# motor_line.net
KiCad netlist of a schematic drawn in EAGLE
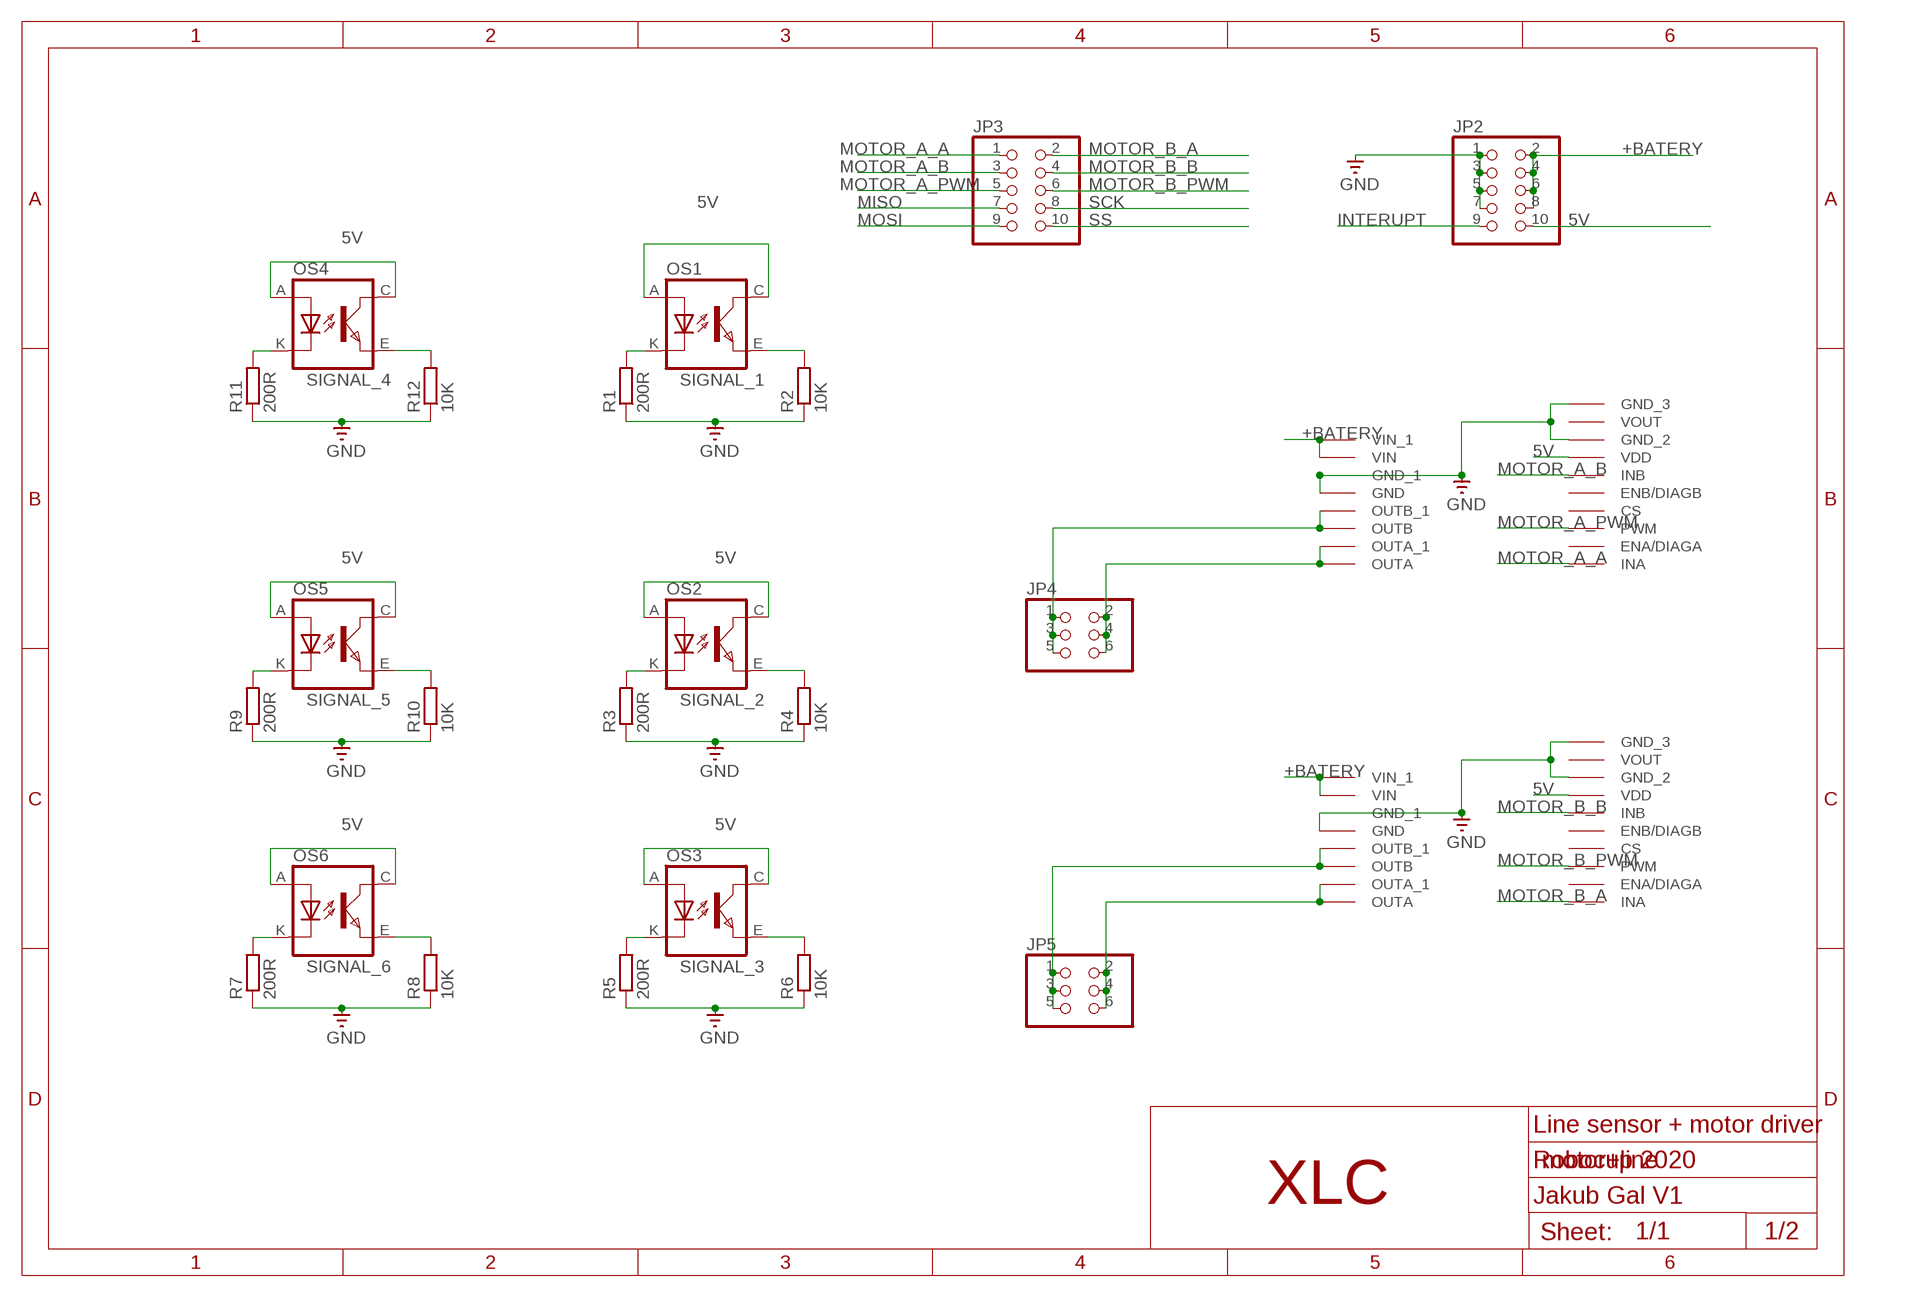
[diagram p0: schematic, sheet 1, part 1 of 2]
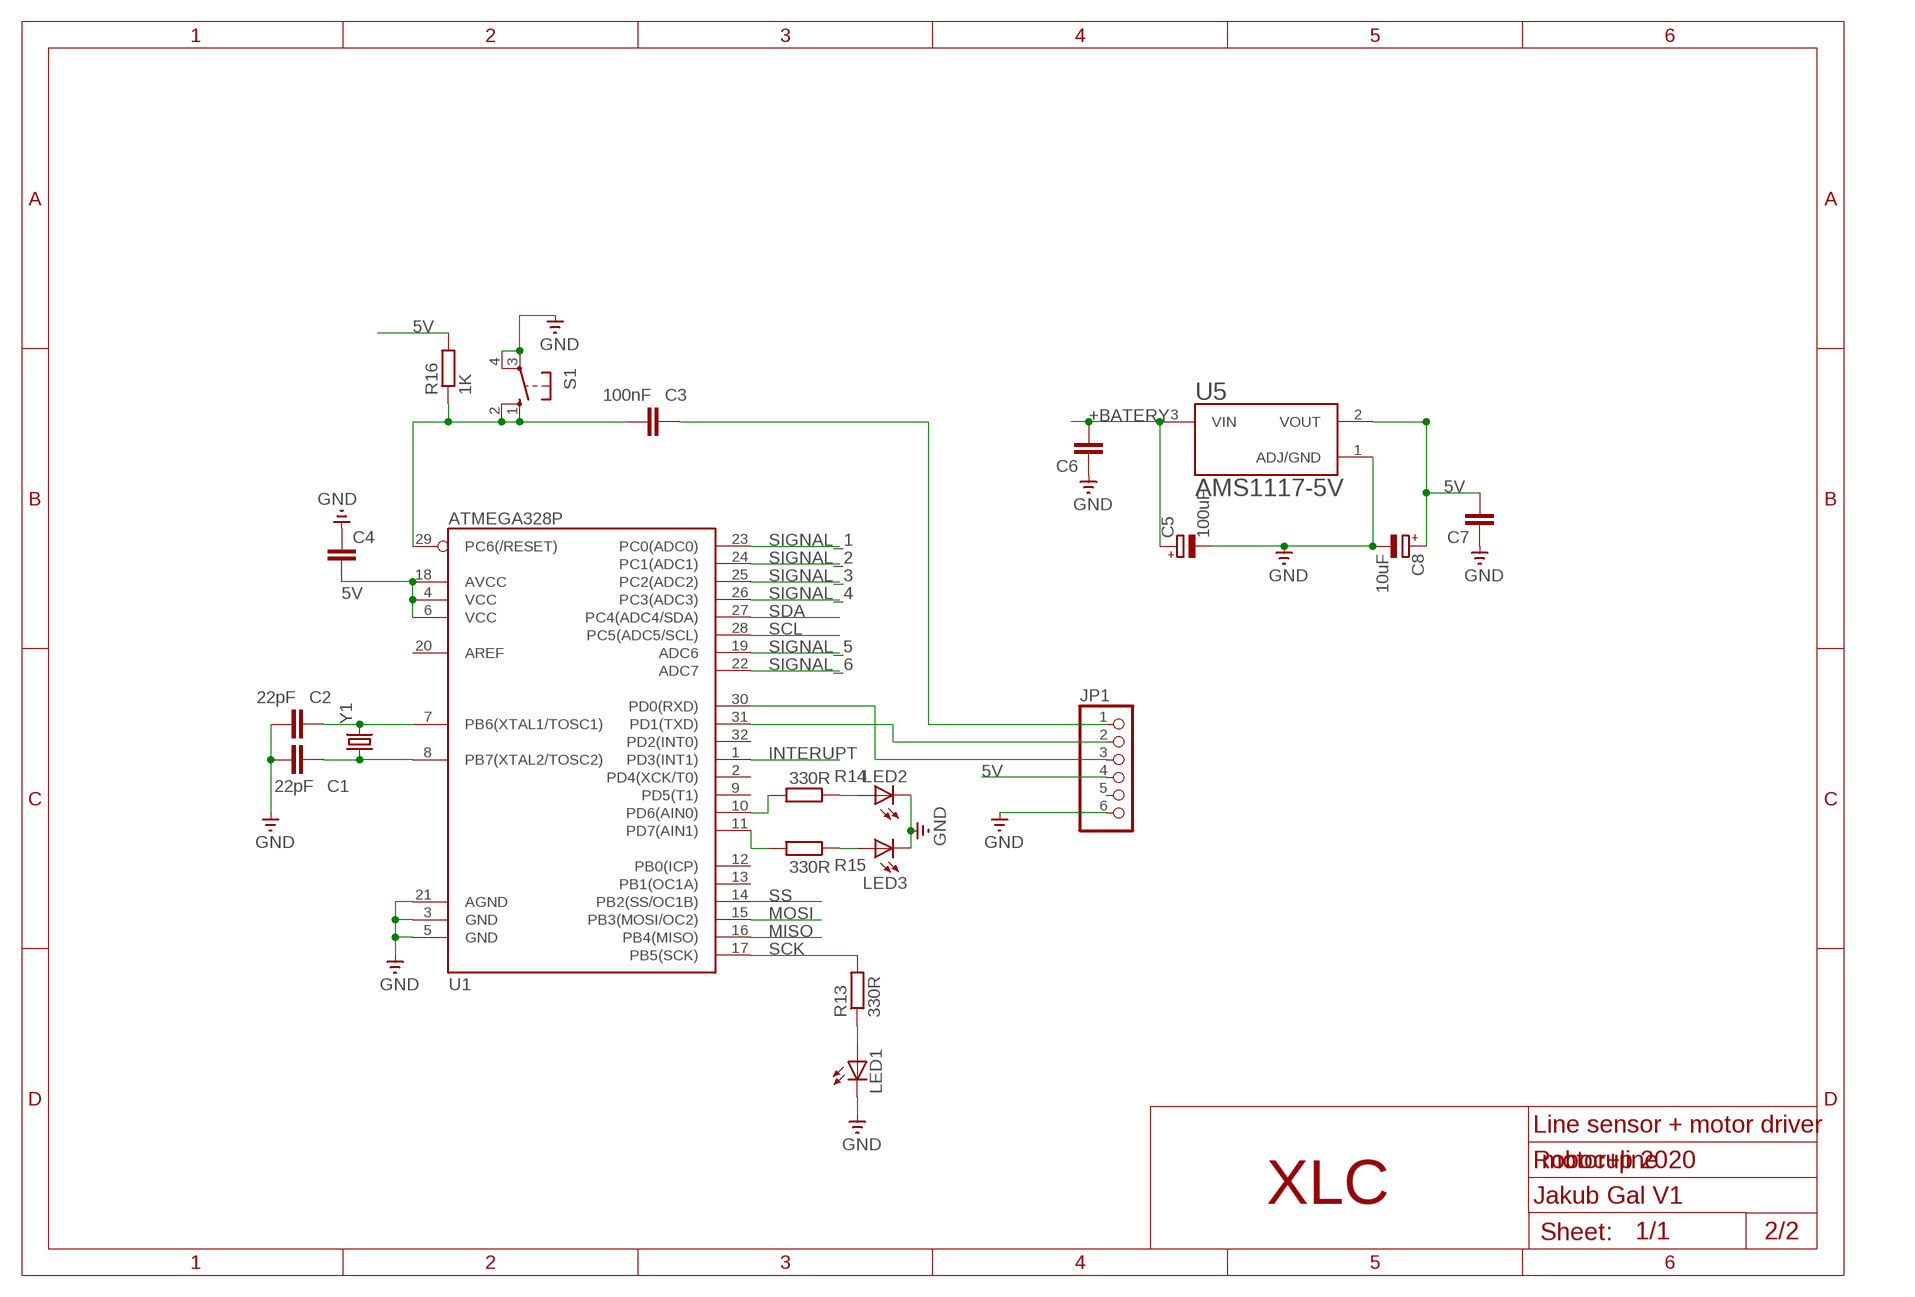
[diagram p1: schematic, sheet 1, part 2 of 2]

(export (version "E")
  (design (tool "Eeschema 10.0.6"))
  (components
    (comp (ref "C1")
      (value "22pF")
      (footprint "eagle-import:C0603")
      (libsource (lib "eagle-import") (part "C-EUC0603"))
    )
    (comp (ref "C2")
      (value "22pF")
      (footprint "eagle-import:C0603")
      (libsource (lib "eagle-import") (part "C-EUC0603"))
    )
    (comp (ref "C3")
      (value "100nF")
      (footprint "eagle-import:C0603")
      (libsource (lib "eagle-import") (part "C-EUC0603"))
    )
    (comp (ref "C4")
      (value "C-EUC0603")
      (footprint "eagle-import:C0603")
      (libsource (lib "eagle-import") (part "rcl_334_C-EUC0603"))
    )
    (comp (ref "C5")
      (value "100uF")
      (footprint "eagle-import:UD-6,3X7,7_NICHICON")
      (libsource (lib "eagle-import") (part "CPOL-EUUD-6,3X7,7"))
    )
    (comp (ref "C6")
      (value "C-EUC0603")
      (footprint "eagle-import:C0603")
      (libsource (lib "eagle-import") (part "rcl_334_C-EUC0603"))
    )
    (comp (ref "C7")
      (value "C-EUC0603")
      (footprint "eagle-import:C0603")
      (libsource (lib "eagle-import") (part "rcl_334_C-EUC0603"))
    )
    (comp (ref "C8")
      (value "10uF")
      (footprint "eagle-import:UD-4X5,8_NICHICON")
      (libsource (lib "eagle-import") (part "CPOL-EUUD-4X5,8"))
    )
    (comp (ref "JP1")
      (value "PINHD-1X6/90")
      (footprint "eagle-import:1X06_90")
      (libsource (lib "eagle-import") (part "PINHD-1X6/90"))
    )
    (comp (ref "JP2")
      (value "PINHD-2X5")
      (footprint "eagle-import:2X05")
      (libsource (lib "eagle-import") (part "PINHD-2X5"))
    )
    (comp (ref "JP3")
      (value "PINHD-2X5")
      (footprint "eagle-import:2X05")
      (libsource (lib "eagle-import") (part "PINHD-2X5"))
    )
    (comp (ref "JP4")
      (value "PINHD-2X3")
      (footprint "eagle-import:2X03")
      (libsource (lib "eagle-import") (part "PINHD-2X3"))
    )
    (comp (ref "JP5")
      (value "PINHD-2X3")
      (footprint "eagle-import:2X03")
      (libsource (lib "eagle-import") (part "PINHD-2X3"))
    )
    (comp (ref "LED1")
      (value "LEDCHIPLED_0603")
      (footprint "eagle-import:CHIPLED_0603")
      (libsource (lib "eagle-import") (part "LEDCHIPLED_0603"))
    )
    (comp (ref "LED2")
      (value "LEDCHIPLED_0603")
      (footprint "eagle-import:CHIPLED_0603")
      (libsource (lib "eagle-import") (part "LEDCHIPLED_0603"))
    )
    (comp (ref "LED3")
      (value "LEDCHIPLED_0603")
      (footprint "eagle-import:CHIPLED_0603")
      (libsource (lib "eagle-import") (part "LEDCHIPLED_0603"))
    )
    (comp (ref "OS1")
      (value "TCRT5000")
      (footprint "eagle-import:TCRT5000")
      (libsource (lib "eagle-import") (part "TCRT5000"))
    )
    (comp (ref "OS2")
      (value "TCRT5000")
      (footprint "eagle-import:TCRT5000")
      (libsource (lib "eagle-import") (part "TCRT5000"))
    )
    (comp (ref "OS3")
      (value "TCRT5000")
      (footprint "eagle-import:TCRT5000")
      (libsource (lib "eagle-import") (part "TCRT5000"))
    )
    (comp (ref "OS4")
      (value "TCRT5000")
      (footprint "eagle-import:TCRT5000")
      (fields (field (name "SPICEPREFIX") "O"))
      (libsource (lib "eagle-import") (part "TCRT5000"))
    )
    (comp (ref "OS5")
      (value "TCRT5000")
      (footprint "eagle-import:TCRT5000")
      (libsource (lib "eagle-import") (part "TCRT5000"))
    )
    (comp (ref "OS6")
      (value "TCRT5000")
      (footprint "eagle-import:TCRT5000")
      (fields (field (name "SPICEPREFIX") "O"))
      (libsource (lib "eagle-import") (part "TCRT5000"))
    )
    (comp (ref "R1")
      (value "200R")
      (footprint "eagle-import:R0603")
      (libsource (lib "eagle-import") (part "R-EU_R0603"))
    )
    (comp (ref "R2")
      (value "10K")
      (footprint "eagle-import:R0603")
      (libsource (lib "eagle-import") (part "R-EU_R0603"))
    )
    (comp (ref "R3")
      (value "200R")
      (footprint "eagle-import:R0603")
      (libsource (lib "eagle-import") (part "R-EU_R0603"))
    )
    (comp (ref "R4")
      (value "10K")
      (footprint "eagle-import:R0603")
      (libsource (lib "eagle-import") (part "R-EU_R0603"))
    )
    (comp (ref "R5")
      (value "200R")
      (footprint "eagle-import:R0603")
      (libsource (lib "eagle-import") (part "R-EU_R0603"))
    )
    (comp (ref "R6")
      (value "10K")
      (footprint "eagle-import:R0603")
      (libsource (lib "eagle-import") (part "R-EU_R0603"))
    )
    (comp (ref "R7")
      (value "200R")
      (footprint "eagle-import:R0603")
      (libsource (lib "eagle-import") (part "R-EU_R0603"))
    )
    (comp (ref "R8")
      (value "10K")
      (footprint "eagle-import:R0603")
      (libsource (lib "eagle-import") (part "R-EU_R0603"))
    )
    (comp (ref "R9")
      (value "200R")
      (footprint "eagle-import:R0603")
      (libsource (lib "eagle-import") (part "R-EU_R0603"))
    )
    (comp (ref "R10")
      (value "10K")
      (footprint "eagle-import:R0603")
      (libsource (lib "eagle-import") (part "R-EU_R0603"))
    )
    (comp (ref "R11")
      (value "200R")
      (footprint "eagle-import:R0603")
      (libsource (lib "eagle-import") (part "R-EU_R0603"))
    )
    (comp (ref "R12")
      (value "10K")
      (footprint "eagle-import:R0603")
      (libsource (lib "eagle-import") (part "R-EU_R0603"))
    )
    (comp (ref "R13")
      (value "330R")
      (footprint "eagle-import:R0603")
      (libsource (lib "eagle-import") (part "R-EU_R0603"))
    )
    (comp (ref "R14")
      (value "330R")
      (footprint "eagle-import:R0603")
      (libsource (lib "eagle-import") (part "R-EU_R0603"))
    )
    (comp (ref "R15")
      (value "330R")
      (footprint "eagle-import:R0603")
      (libsource (lib "eagle-import") (part "R-EU_R0603"))
    )
    (comp (ref "R16")
      (value "1K")
      (footprint "eagle-import:R0603")
      (libsource (lib "eagle-import") (part "R-EU_R0603"))
    )
    (comp (ref "S1")
      (value "10-XX")
      (footprint "eagle-import:B3F-10XX")
      (fields (field (name "MPN") "B3F-1000"))
      (libsource (lib "eagle-import") (part "10-XX"))
    )
    (comp (ref "U$1")
      (value "MOTOR_DRIVER")
      (footprint "eagle-import:MOTOR_DRIVER")
      (libsource (lib "eagle-import") (part "MOTOR_DRIVER"))
    )
    (comp (ref "U$2")
      (value "MOTOR_DRIVER")
      (footprint "eagle-import:MOTOR_DRIVER")
      (libsource (lib "eagle-import") (part "MOTOR_DRIVER"))
    )
    (comp (ref "U1")
      (value "ATMEGA328P")
      (footprint "eagle-import:TQFP32-08")
      (libsource (lib "eagle-import") (part "ATMEGA328_SMT"))
    )
    (comp (ref "U5")
      (value "AMS1117-5V")
      (footprint "eagle-import:SOT229P700X180-4N")
      (fields (field (name "MF") "Advanced Monolithic Systems") (field (name "MP") "AMS1117-3.3"))
      (libsource (lib "eagle-import") (part "AMS1117-3.3"))
    )
    (comp (ref "Y1")
      (value "CRYSTALHC49US")
      (footprint "eagle-import:HC49US")
      (libsource (lib "eagle-import") (part "CRYSTALHC49US"))
    )
  )
  (nets
    (net (code "1") (name "/+BATERY") (class "Default")
      (node (ref "C5") (pin "+") (pinfunction "+_+") (pintype "passive"))
      (node (ref "C6") (pin "2") (pinfunction "2_2") (pintype "passive"))
      (node (ref "JP2") (pin "2") (pinfunction "2_2") (pintype "passive"))
      (node (ref "JP2") (pin "4") (pinfunction "4_4") (pintype "passive"))
      (node (ref "JP2") (pin "6") (pinfunction "6_6") (pintype "passive"))
      (node (ref "JP2") (pin "8") (pinfunction "8_8") (pintype "passive"))
      (node (ref "U$1") (pin "VIN") (pinfunction "VIN_VIN") (pintype "bidirectional"))
      (node (ref "U$1") (pin "VIN_1") (pinfunction "VIN_1_VIN_1") (pintype "bidirectional"))
      (node (ref "U$2") (pin "VIN") (pinfunction "VIN_VIN") (pintype "bidirectional"))
      (node (ref "U$2") (pin "VIN_1") (pinfunction "VIN_1_VIN_1") (pintype "bidirectional"))
      (node (ref "U5") (pin "3") (pinfunction "VIN_3") (pintype "input"))
    )
    (net (code "2") (name "/5V") (class "Default")
      (node (ref "C4") (pin "2") (pinfunction "2_2") (pintype "passive"))
      (node (ref "C7") (pin "2") (pinfunction "2_2") (pintype "passive"))
      (node (ref "C8") (pin "+") (pinfunction "+_+") (pintype "passive"))
      (node (ref "JP1") (pin "4") (pinfunction "4_4") (pintype "passive"))
      (node (ref "JP2") (pin "10") (pinfunction "10_10") (pintype "passive"))
      (node (ref "OS1") (pin "A") (pinfunction "ANODE_A") (pintype "passive"))
      (node (ref "OS1") (pin "C") (pinfunction "COLLECTOR_C") (pintype "passive"))
      (node (ref "OS2") (pin "A") (pinfunction "ANODE_A") (pintype "passive"))
      (node (ref "OS2") (pin "C") (pinfunction "COLLECTOR_C") (pintype "passive"))
      (node (ref "OS3") (pin "A") (pinfunction "ANODE_A") (pintype "passive"))
      (node (ref "OS3") (pin "C") (pinfunction "COLLECTOR_C") (pintype "passive"))
      (node (ref "OS4") (pin "A") (pinfunction "ANODE_A") (pintype "passive"))
      (node (ref "OS4") (pin "C") (pinfunction "COLLECTOR_C") (pintype "passive"))
      (node (ref "OS5") (pin "A") (pinfunction "ANODE_A") (pintype "passive"))
      (node (ref "OS5") (pin "C") (pinfunction "COLLECTOR_C") (pintype "passive"))
      (node (ref "OS6") (pin "A") (pinfunction "ANODE_A") (pintype "passive"))
      (node (ref "OS6") (pin "C") (pinfunction "COLLECTOR_C") (pintype "passive"))
      (node (ref "R16") (pin "2") (pinfunction "2_2") (pintype "passive"))
      (node (ref "U$1") (pin "VDD") (pinfunction "VDD_VDD") (pintype "bidirectional"))
      (node (ref "U$2") (pin "VDD") (pinfunction "VDD_VDD") (pintype "bidirectional"))
      (node (ref "U1") (pin "18") (pinfunction "AVCC_18") (pintype "bidirectional"))
      (node (ref "U1") (pin "4") (pinfunction "VCC_4") (pintype "bidirectional"))
      (node (ref "U1") (pin "6") (pinfunction "VCC_6") (pintype "bidirectional"))
      (node (ref "U5") (pin "2") (pinfunction "VOUT_2") (pintype "output"))
    )
    (net (code "3") (name "/INTERUPT") (class "Default")
      (node (ref "JP2") (pin "9") (pinfunction "9_9") (pintype "passive"))
      (node (ref "U1") (pin "1") (pinfunction "PD3(INT1)_1") (pintype "bidirectional"))
    )
    (net (code "4") (name "/MISO") (class "Default")
      (node (ref "JP3") (pin "7") (pinfunction "7_7") (pintype "passive"))
      (node (ref "U1") (pin "16") (pinfunction "PB4(MISO)_16") (pintype "bidirectional"))
    )
    (net (code "5") (name "/MOSI") (class "Default")
      (node (ref "JP3") (pin "9") (pinfunction "9_9") (pintype "passive"))
      (node (ref "U1") (pin "15") (pinfunction "PB3(MOSI/OC2)_15") (pintype "bidirectional"))
    )
    (net (code "6") (name "/MOTOR_A_A") (class "Default")
      (node (ref "JP3") (pin "1") (pinfunction "1_1") (pintype "passive"))
      (node (ref "U$1") (pin "INA") (pinfunction "INA_INA") (pintype "bidirectional"))
    )
    (net (code "7") (name "/MOTOR_A_B") (class "Default")
      (node (ref "JP3") (pin "3") (pinfunction "3_3") (pintype "passive"))
      (node (ref "U$1") (pin "INB") (pinfunction "INB_INB") (pintype "bidirectional"))
    )
    (net (code "8") (name "/MOTOR_A_PWM") (class "Default")
      (node (ref "JP3") (pin "5") (pinfunction "5_5") (pintype "passive"))
      (node (ref "U$1") (pin "PWM") (pinfunction "PWM_PWM") (pintype "bidirectional"))
    )
    (net (code "9") (name "/MOTOR_B_A") (class "Default")
      (node (ref "JP3") (pin "2") (pinfunction "2_2") (pintype "passive"))
      (node (ref "U$2") (pin "INA") (pinfunction "INA_INA") (pintype "bidirectional"))
    )
    (net (code "10") (name "/MOTOR_B_B") (class "Default")
      (node (ref "JP3") (pin "4") (pinfunction "4_4") (pintype "passive"))
      (node (ref "U$2") (pin "INB") (pinfunction "INB_INB") (pintype "bidirectional"))
    )
    (net (code "11") (name "/MOTOR_B_PWM") (class "Default")
      (node (ref "JP3") (pin "6") (pinfunction "6_6") (pintype "passive"))
      (node (ref "U$2") (pin "PWM") (pinfunction "PWM_PWM") (pintype "bidirectional"))
    )
    (net (code "12") (name "/SCK") (class "Default")
      (node (ref "JP3") (pin "8") (pinfunction "8_8") (pintype "passive"))
      (node (ref "R13") (pin "2") (pinfunction "2_2") (pintype "passive"))
      (node (ref "U1") (pin "17") (pinfunction "PB5(SCK)_17") (pintype "bidirectional"))
    )
    (net (code "13") (name "/SCL") (class "Default")
      (node (ref "U1") (pin "28") (pinfunction "PC5(ADC5/SCL)_28") (pintype "bidirectional"))
    )
    (net (code "14") (name "/SDA") (class "Default")
      (node (ref "U1") (pin "27") (pinfunction "PC4(ADC4/SDA)_27") (pintype "bidirectional"))
    )
    (net (code "15") (name "/SIGNAL_1") (class "Default")
      (node (ref "OS1") (pin "E") (pinfunction "EMITTER_E") (pintype "passive"))
      (node (ref "R2") (pin "2") (pinfunction "2_2") (pintype "passive"))
      (node (ref "U1") (pin "23") (pinfunction "PC0(ADC0)_23") (pintype "bidirectional"))
    )
    (net (code "16") (name "/SIGNAL_2") (class "Default")
      (node (ref "OS2") (pin "E") (pinfunction "EMITTER_E") (pintype "passive"))
      (node (ref "R4") (pin "2") (pinfunction "2_2") (pintype "passive"))
      (node (ref "U1") (pin "24") (pinfunction "PC1(ADC1)_24") (pintype "bidirectional"))
    )
    (net (code "17") (name "/SIGNAL_3") (class "Default")
      (node (ref "OS3") (pin "E") (pinfunction "EMITTER_E") (pintype "passive"))
      (node (ref "R6") (pin "2") (pinfunction "2_2") (pintype "passive"))
      (node (ref "U1") (pin "25") (pinfunction "PC2(ADC2)_25") (pintype "bidirectional"))
    )
    (net (code "18") (name "/SIGNAL_4") (class "Default")
      (node (ref "OS4") (pin "E") (pinfunction "EMITTER_E") (pintype "passive"))
      (node (ref "R12") (pin "2") (pinfunction "2_2") (pintype "passive"))
      (node (ref "U1") (pin "26") (pinfunction "PC3(ADC3)_26") (pintype "bidirectional"))
    )
    (net (code "19") (name "/SIGNAL_5") (class "Default")
      (node (ref "OS5") (pin "E") (pinfunction "EMITTER_E") (pintype "passive"))
      (node (ref "R10") (pin "2") (pinfunction "2_2") (pintype "passive"))
      (node (ref "U1") (pin "19") (pinfunction "ADC6_19") (pintype "bidirectional"))
    )
    (net (code "20") (name "/SIGNAL_6") (class "Default")
      (node (ref "OS6") (pin "E") (pinfunction "EMITTER_E") (pintype "passive"))
      (node (ref "R8") (pin "2") (pinfunction "2_2") (pintype "passive"))
      (node (ref "U1") (pin "22") (pinfunction "ADC7_22") (pintype "bidirectional"))
    )
    (net (code "21") (name "/SS") (class "Default")
      (node (ref "JP3") (pin "10") (pinfunction "10_10") (pintype "passive"))
      (node (ref "U1") (pin "14") (pinfunction "PB2(SS/OC1B)_14") (pintype "bidirectional"))
    )
    (net (code "22") (name "GND") (class "Default")
      (node (ref "C1") (pin "1") (pinfunction "1_1") (pintype "passive"))
      (node (ref "C2") (pin "1") (pinfunction "1_1") (pintype "passive"))
      (node (ref "C4") (pin "1") (pinfunction "1_1") (pintype "passive"))
      (node (ref "C5") (pin "-") (pinfunction "-_-") (pintype "passive"))
      (node (ref "C6") (pin "1") (pinfunction "1_1") (pintype "passive"))
      (node (ref "C7") (pin "1") (pinfunction "1_1") (pintype "passive"))
      (node (ref "C8") (pin "-") (pinfunction "-_-") (pintype "passive"))
      (node (ref "JP1") (pin "6") (pinfunction "6_6") (pintype "passive"))
      (node (ref "JP2") (pin "1") (pinfunction "1_1") (pintype "passive"))
      (node (ref "JP2") (pin "3") (pinfunction "3_3") (pintype "passive"))
      (node (ref "JP2") (pin "5") (pinfunction "5_5") (pintype "passive"))
      (node (ref "JP2") (pin "7") (pinfunction "7_7") (pintype "passive"))
      (node (ref "LED1") (pin "C") (pinfunction "C_C") (pintype "passive"))
      (node (ref "LED2") (pin "C") (pinfunction "C_C") (pintype "passive"))
      (node (ref "LED3") (pin "C") (pinfunction "C_C") (pintype "passive"))
      (node (ref "R1") (pin "1") (pinfunction "1_1") (pintype "passive"))
      (node (ref "R10") (pin "1") (pinfunction "1_1") (pintype "passive"))
      (node (ref "R11") (pin "1") (pinfunction "1_1") (pintype "passive"))
      (node (ref "R12") (pin "1") (pinfunction "1_1") (pintype "passive"))
      (node (ref "R2") (pin "1") (pinfunction "1_1") (pintype "passive"))
      (node (ref "R3") (pin "1") (pinfunction "1_1") (pintype "passive"))
      (node (ref "R4") (pin "1") (pinfunction "1_1") (pintype "passive"))
      (node (ref "R5") (pin "1") (pinfunction "1_1") (pintype "passive"))
      (node (ref "R6") (pin "1") (pinfunction "1_1") (pintype "passive"))
      (node (ref "R7") (pin "1") (pinfunction "1_1") (pintype "passive"))
      (node (ref "R8") (pin "1") (pinfunction "1_1") (pintype "passive"))
      (node (ref "R9") (pin "1") (pinfunction "1_1") (pintype "passive"))
      (node (ref "S1") (pin "3") (pinfunction "P_3") (pintype "passive"))
      (node (ref "S1") (pin "4") (pinfunction "P1_4") (pintype "passive"))
      (node (ref "U$1") (pin "GND") (pinfunction "GND_GND") (pintype "bidirectional"))
      (node (ref "U$1") (pin "GND_1") (pinfunction "GND_1_GND_1") (pintype "bidirectional"))
      (node (ref "U$1") (pin "GND_2") (pinfunction "GND_2_GND_2") (pintype "bidirectional"))
      (node (ref "U$1") (pin "GND_3") (pinfunction "GND_3_GND_3") (pintype "bidirectional"))
      (node (ref "U$2") (pin "GND") (pinfunction "GND_GND") (pintype "bidirectional"))
      (node (ref "U$2") (pin "GND_1") (pinfunction "GND_1_GND_1") (pintype "bidirectional"))
      (node (ref "U$2") (pin "GND_2") (pinfunction "GND_2_GND_2") (pintype "bidirectional"))
      (node (ref "U$2") (pin "GND_3") (pinfunction "GND_3_GND_3") (pintype "bidirectional"))
      (node (ref "U1") (pin "21") (pinfunction "AGND_21") (pintype "bidirectional"))
      (node (ref "U1") (pin "3") (pinfunction "GND_3") (pintype "bidirectional"))
      (node (ref "U1") (pin "5") (pinfunction "GND_5") (pintype "bidirectional"))
      (node (ref "U5") (pin "1") (pinfunction "ADJ/GND_1") (pintype "power_in"))
    )
    (net (code "23") (name "Net-(C3-Pad2)") (class "Default")
      (node (ref "C3") (pin "2") (pinfunction "2_2") (pintype "passive"))
      (node (ref "JP1") (pin "1") (pinfunction "1_1") (pintype "passive"))
    )
    (net (code "24") (name "Net-(JP4-Pad1)") (class "Default")
      (node (ref "JP4") (pin "1") (pinfunction "1_1") (pintype "passive"))
      (node (ref "JP4") (pin "3") (pinfunction "3_3") (pintype "passive"))
      (node (ref "JP4") (pin "5") (pinfunction "5_5") (pintype "passive"))
      (node (ref "U$1") (pin "OUTB") (pinfunction "OUTB_OUTB") (pintype "bidirectional"))
      (node (ref "U$1") (pin "OUTB_1") (pinfunction "OUTB_1_OUTB_1") (pintype "bidirectional"))
    )
    (net (code "25") (name "Net-(JP4-Pad2)") (class "Default")
      (node (ref "JP4") (pin "2") (pinfunction "2_2") (pintype "passive"))
      (node (ref "JP4") (pin "4") (pinfunction "4_4") (pintype "passive"))
      (node (ref "JP4") (pin "6") (pinfunction "6_6") (pintype "passive"))
      (node (ref "U$1") (pin "OUTA") (pinfunction "OUTA_OUTA") (pintype "bidirectional"))
      (node (ref "U$1") (pin "OUTA_1") (pinfunction "OUTA_1_OUTA_1") (pintype "bidirectional"))
    )
    (net (code "26") (name "Net-(JP5-Pad1)") (class "Default")
      (node (ref "JP5") (pin "1") (pinfunction "1_1") (pintype "passive"))
      (node (ref "JP5") (pin "3") (pinfunction "3_3") (pintype "passive"))
      (node (ref "JP5") (pin "5") (pinfunction "5_5") (pintype "passive"))
      (node (ref "U$2") (pin "OUTB") (pinfunction "OUTB_OUTB") (pintype "bidirectional"))
      (node (ref "U$2") (pin "OUTB_1") (pinfunction "OUTB_1_OUTB_1") (pintype "bidirectional"))
    )
    (net (code "27") (name "Net-(JP5-Pad2)") (class "Default")
      (node (ref "JP5") (pin "2") (pinfunction "2_2") (pintype "passive"))
      (node (ref "JP5") (pin "4") (pinfunction "4_4") (pintype "passive"))
      (node (ref "JP5") (pin "6") (pinfunction "6_6") (pintype "passive"))
      (node (ref "U$2") (pin "OUTA") (pinfunction "OUTA_OUTA") (pintype "bidirectional"))
      (node (ref "U$2") (pin "OUTA_1") (pinfunction "OUTA_1_OUTA_1") (pintype "bidirectional"))
    )
    (net (code "28") (name "Net-(LED1-PadA)") (class "Default")
      (node (ref "LED1") (pin "A") (pinfunction "A_A") (pintype "passive"))
      (node (ref "R13") (pin "1") (pinfunction "1_1") (pintype "passive"))
    )
    (net (code "29") (name "Net-(LED2-PadA)") (class "Default")
      (node (ref "LED2") (pin "A") (pinfunction "A_A") (pintype "passive"))
      (node (ref "R14") (pin "1") (pinfunction "1_1") (pintype "passive"))
    )
    (net (code "30") (name "Net-(LED3-PadA)") (class "Default")
      (node (ref "LED3") (pin "A") (pinfunction "A_A") (pintype "passive"))
      (node (ref "R15") (pin "1") (pinfunction "1_1") (pintype "passive"))
    )
    (net (code "31") (name "Net-(OS1-CATHODE)") (class "Default")
      (node (ref "OS1") (pin "K") (pinfunction "CATHODE_K") (pintype "passive"))
      (node (ref "R1") (pin "2") (pinfunction "2_2") (pintype "passive"))
    )
    (net (code "32") (name "Net-(OS2-CATHODE)") (class "Default")
      (node (ref "OS2") (pin "K") (pinfunction "CATHODE_K") (pintype "passive"))
      (node (ref "R3") (pin "2") (pinfunction "2_2") (pintype "passive"))
    )
    (net (code "33") (name "Net-(OS3-CATHODE)") (class "Default")
      (node (ref "OS3") (pin "K") (pinfunction "CATHODE_K") (pintype "passive"))
      (node (ref "R5") (pin "2") (pinfunction "2_2") (pintype "passive"))
    )
    (net (code "34") (name "Net-(OS4-CATHODE)") (class "Default")
      (node (ref "OS4") (pin "K") (pinfunction "CATHODE_K") (pintype "passive"))
      (node (ref "R11") (pin "2") (pinfunction "2_2") (pintype "passive"))
    )
    (net (code "35") (name "Net-(OS5-CATHODE)") (class "Default")
      (node (ref "OS5") (pin "K") (pinfunction "CATHODE_K") (pintype "passive"))
      (node (ref "R9") (pin "2") (pinfunction "2_2") (pintype "passive"))
    )
    (net (code "36") (name "Net-(OS6-CATHODE)") (class "Default")
      (node (ref "OS6") (pin "K") (pinfunction "CATHODE_K") (pintype "passive"))
      (node (ref "R7") (pin "2") (pinfunction "2_2") (pintype "passive"))
    )
    (net (code "37") (name "Net-(S1-S)") (class "Default")
      (node (ref "C3") (pin "1") (pinfunction "1_1") (pintype "passive"))
      (node (ref "R16") (pin "1") (pinfunction "1_1") (pintype "passive"))
      (node (ref "S1") (pin "1") (pinfunction "S_1") (pintype "passive"))
      (node (ref "S1") (pin "2") (pinfunction "S1_2") (pintype "passive"))
      (node (ref "U1") (pin "29") (pinfunction "PC6(/RESET)_29") (pintype "bidirectional"))
    )
    (net (code "38") (name "Net-(U1-PB6(XTAL1{slash}TOSC1))") (class "Default")
      (node (ref "C2") (pin "2") (pinfunction "2_2") (pintype "passive"))
      (node (ref "U1") (pin "7") (pinfunction "PB6(XTAL1/TOSC1)_7") (pintype "bidirectional"))
      (node (ref "Y1") (pin "2") (pinfunction "2_2") (pintype "passive"))
    )
    (net (code "39") (name "Net-(U1-PB7(XTAL2{slash}TOSC2))") (class "Default")
      (node (ref "C1") (pin "2") (pinfunction "2_2") (pintype "passive"))
      (node (ref "U1") (pin "8") (pinfunction "PB7(XTAL2/TOSC2)_8") (pintype "bidirectional"))
      (node (ref "Y1") (pin "1") (pinfunction "1_1") (pintype "passive"))
    )
    (net (code "40") (name "Net-(U1-PD0(RXD))") (class "Default")
      (node (ref "JP1") (pin "3") (pinfunction "3_3") (pintype "passive"))
      (node (ref "U1") (pin "30") (pinfunction "PD0(RXD)_30") (pintype "bidirectional"))
    )
    (net (code "41") (name "Net-(U1-PD1(TXD))") (class "Default")
      (node (ref "JP1") (pin "2") (pinfunction "2_2") (pintype "passive"))
      (node (ref "U1") (pin "31") (pinfunction "PD1(TXD)_31") (pintype "bidirectional"))
    )
    (net (code "42") (name "Net-(U1-PD6(AIN0))") (class "Default")
      (node (ref "R14") (pin "2") (pinfunction "2_2") (pintype "passive"))
      (node (ref "U1") (pin "10") (pinfunction "PD6(AIN0)_10") (pintype "bidirectional"))
    )
    (net (code "43") (name "Net-(U1-PD7(AIN1))") (class "Default")
      (node (ref "R15") (pin "2") (pinfunction "2_2") (pintype "passive"))
      (node (ref "U1") (pin "11") (pinfunction "PD7(AIN1)_11") (pintype "bidirectional"))
    )
    (net (code "44") (name "unconnected-(JP1-Pad5)") (class "Default")
      (node (ref "JP1") (pin "5") (pinfunction "5_5") (pintype "passive"))
    )
    (net (code "45") (name "unconnected-(U$1-PadCS)") (class "Default")
      (node (ref "U$1") (pin "CS") (pinfunction "CS_CS") (pintype "bidirectional"))
    )
    (net (code "46") (name "unconnected-(U$1-PadENA{slash}DIAGA)") (class "Default")
      (node (ref "U$1") (pin "ENA/DIAGA") (pinfunction "ENA/DIAGA_ENA/DIAGA") (pintype "bidirectional"))
    )
    (net (code "47") (name "unconnected-(U$1-PadENB{slash}DIAGB)") (class "Default")
      (node (ref "U$1") (pin "ENB/DIAGB") (pinfunction "ENB/DIAGB_ENB/DIAGB") (pintype "bidirectional"))
    )
    (net (code "48") (name "unconnected-(U$1-PadVOUT)") (class "Default")
      (node (ref "U$1") (pin "VOUT") (pinfunction "VOUT_VOUT") (pintype "bidirectional"))
    )
    (net (code "49") (name "unconnected-(U$2-PadCS)") (class "Default")
      (node (ref "U$2") (pin "CS") (pinfunction "CS_CS") (pintype "bidirectional"))
    )
    (net (code "50") (name "unconnected-(U$2-PadENA{slash}DIAGA)") (class "Default")
      (node (ref "U$2") (pin "ENA/DIAGA") (pinfunction "ENA/DIAGA_ENA/DIAGA") (pintype "bidirectional"))
    )
    (net (code "51") (name "unconnected-(U$2-PadENB{slash}DIAGB)") (class "Default")
      (node (ref "U$2") (pin "ENB/DIAGB") (pinfunction "ENB/DIAGB_ENB/DIAGB") (pintype "bidirectional"))
    )
    (net (code "52") (name "unconnected-(U$2-PadVOUT)") (class "Default")
      (node (ref "U$2") (pin "VOUT") (pinfunction "VOUT_VOUT") (pintype "bidirectional"))
    )
    (net (code "53") (name "unconnected-(U1-AREF-Pad20)") (class "Default")
      (node (ref "U1") (pin "20") (pinfunction "AREF_20") (pintype "bidirectional"))
    )
    (net (code "54") (name "unconnected-(U1-PB0(ICP)-Pad12)") (class "Default")
      (node (ref "U1") (pin "12") (pinfunction "PB0(ICP)_12") (pintype "bidirectional"))
    )
    (net (code "55") (name "unconnected-(U1-PB1(OC1A)-Pad13)") (class "Default")
      (node (ref "U1") (pin "13") (pinfunction "PB1(OC1A)_13") (pintype "bidirectional"))
    )
    (net (code "56") (name "unconnected-(U1-PD2(INT0)-Pad32)") (class "Default")
      (node (ref "U1") (pin "32") (pinfunction "PD2(INT0)_32") (pintype "bidirectional"))
    )
    (net (code "57") (name "unconnected-(U1-PD4(XCK{slash}T0)-Pad2)") (class "Default")
      (node (ref "U1") (pin "2") (pinfunction "PD4(XCK/T0)_2") (pintype "bidirectional"))
    )
    (net (code "58") (name "unconnected-(U1-PD5(T1)-Pad9)") (class "Default")
      (node (ref "U1") (pin "9") (pinfunction "PD5(T1)_9") (pintype "bidirectional"))
    )
  )
)
